# LogicsOnly_Main.net
KiCad netlist of a schematic drawn in Altium Designer
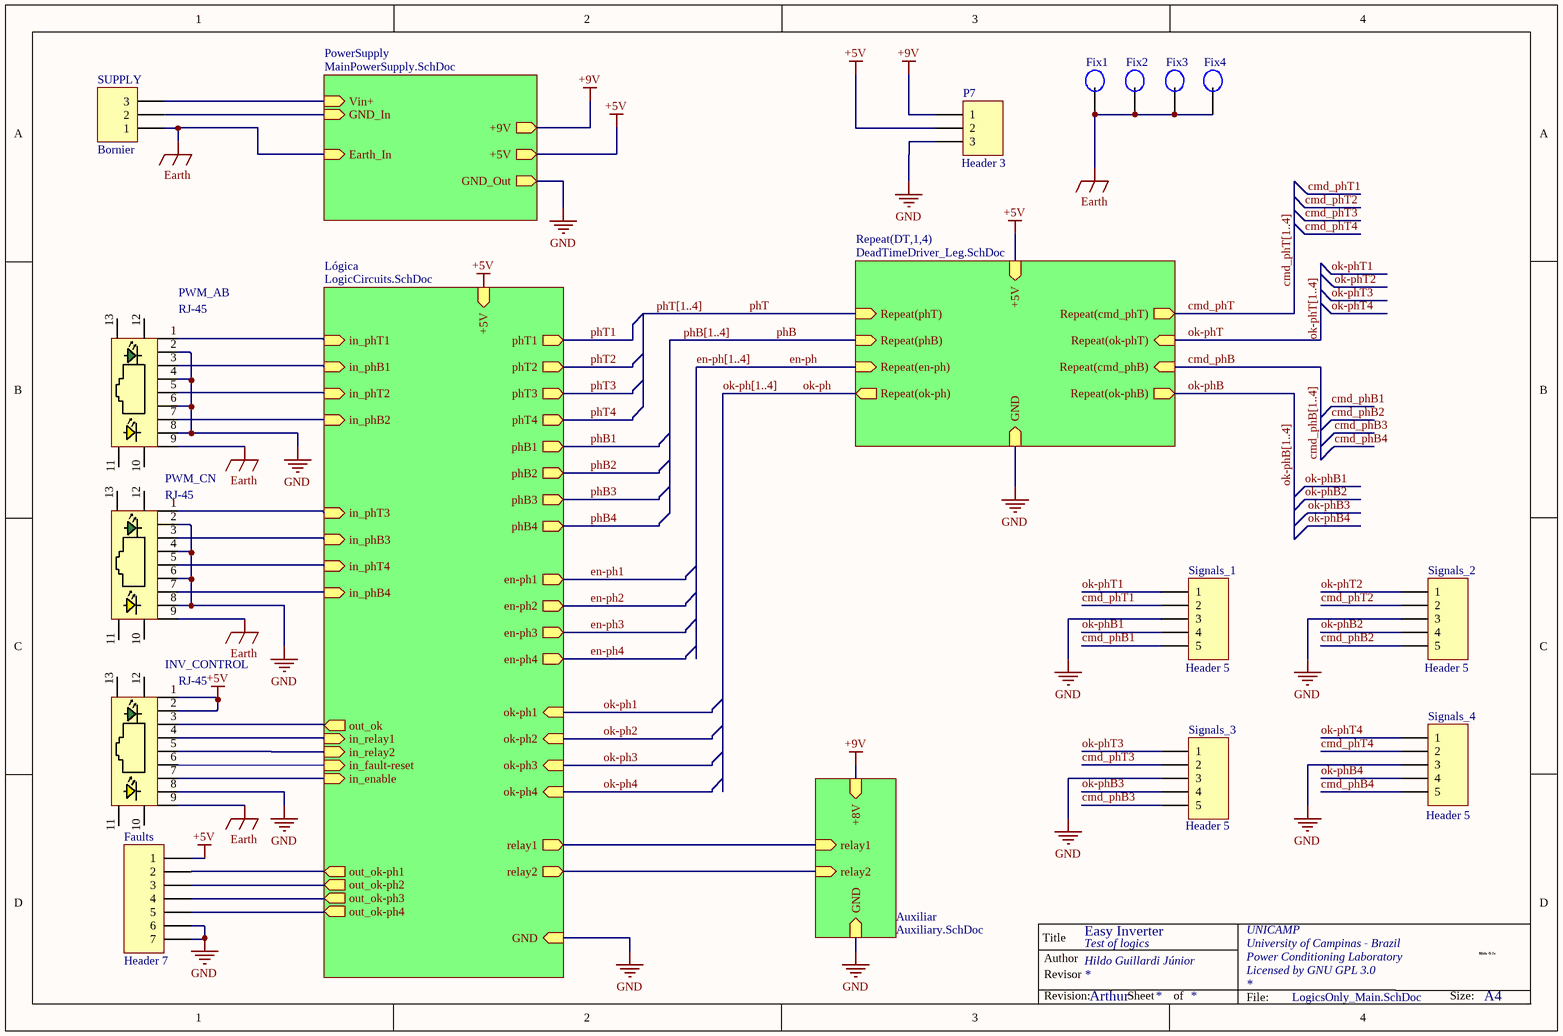
[diagram p0: LogicsOnly_Main.SchDoc]

(export (version "E")
  (design (tool "Eeschema 10.0.6"))
  (components
    (comp (ref "Faults")
      (value "Header 7")
      (description "Header, 7-Pin")
      (libsource (lib "Miscellaneous Connectors") (part "Header 7"))
    )
    (comp (ref "Fix1") (value "~") (footprint "Pino") (libsource (lib "Sch_LCEE") (part "Pino")))
    (comp (ref "Fix2") (value "~") (footprint "Pino") (libsource (lib "Sch_LCEE") (part "Pino")))
    (comp (ref "Fix3") (value "~") (footprint "Pino") (libsource (lib "Sch_LCEE") (part "Pino")))
    (comp (ref "Fix4") (value "~") (footprint "Pino") (libsource (lib "Sch_LCEE") (part "Pino")))
    (comp (ref "INV_CONTROL") (value "RJ-45") (footprint "RJ-45") (libsource (lib "Sch_LCEE") (part "RJ-45")))
    (comp (ref "P7")
      (value "Header 3")
      (footprint "HDR1X3")
      (description "Header, 3-Pin")
      (libsource (lib "") (part "Header 3_1"))
    )
    (comp (ref "PWM_AB") (value "RJ-45") (footprint "RJ-45") (libsource (lib "Sch_LCEE") (part "RJ-45")))
    (comp (ref "PWM_CN") (value "RJ-45") (footprint "RJ-45") (libsource (lib "Sch_LCEE") (part "RJ-45")))
    (comp (ref "Signals_1")
      (value "Header 5")
      (footprint "HDR1X5")
      (description "Header, 5-Pin")
      (libsource (lib "Miscellaneous Connectors") (part "Header 5"))
    )
    (comp (ref "Signals_2")
      (value "Header 5")
      (footprint "HDR1X5")
      (description "Header, 5-Pin")
      (libsource (lib "Miscellaneous Connectors") (part "Header 5"))
    )
    (comp (ref "Signals_3")
      (value "Header 5")
      (footprint "HDR1X5")
      (description "Header, 5-Pin")
      (libsource (lib "Miscellaneous Connectors") (part "Header 5"))
    )
    (comp (ref "Signals_4")
      (value "Header 5")
      (footprint "HDR1X5")
      (description "Header, 5-Pin")
      (libsource (lib "Miscellaneous Connectors") (part "Header 5"))
    )
    (comp (ref "SUPPLY")
      (value "Bornier")
      (footprint "3 Pin  Borner")
      (description "Header, 3-Pin")
      (libsource (lib "AQAC") (part "Header 3"))
    )
  )
  (nets
    (net (code "1") (name "+5V") (class "Default")
      (node (ref "Faults") (pin "1") (pinfunction "1_1") (pintype "passive"))
      (node (ref "INV_CONTROL") (pin "1") (pinfunction "1_1") (pintype "passive"))
      (node (ref "INV_CONTROL") (pin "2") (pinfunction "2_2") (pintype "passive"))
      (node (ref "P7") (pin "2") (pinfunction "2_2") (pintype "passive"))
    )
    (net (code "2") (name "+9V") (class "Default")
      (node (ref "P7") (pin "1") (pinfunction "1_1") (pintype "passive"))
    )
    (net (code "3") (name "/GND_In") (class "Default")
      (node (ref "SUPPLY") (pin "2") (pinfunction "2_2") (pintype "passive"))
    )
    (net (code "4") (name "/Vin+") (class "Default")
      (node (ref "SUPPLY") (pin "3") (pinfunction "3_3") (pintype "passive"))
    )
    (net (code "6") (name "/cmd_phB1") (class "Default")
      (node (ref "Signals_1") (pin "5") (pinfunction "5_5") (pintype "passive"))
    )
    (net (code "7") (name "/cmd_phB2") (class "Default")
      (node (ref "Signals_2") (pin "5") (pinfunction "5_5") (pintype "passive"))
    )
    (net (code "8") (name "/cmd_phB3") (class "Default")
      (node (ref "Signals_3") (pin "5") (pinfunction "5_5") (pintype "passive"))
    )
    (net (code "9") (name "/cmd_phB4") (class "Default")
      (node (ref "Signals_4") (pin "5") (pinfunction "5_5") (pintype "passive"))
    )
    (net (code "12") (name "/cmd_phT1") (class "Default")
      (node (ref "Signals_1") (pin "2") (pinfunction "2_2") (pintype "passive"))
    )
    (net (code "13") (name "/cmd_phT2") (class "Default")
      (node (ref "Signals_2") (pin "2") (pinfunction "2_2") (pintype "passive"))
    )
    (net (code "14") (name "/cmd_phT3") (class "Default")
      (node (ref "Signals_3") (pin "2") (pinfunction "2_2") (pintype "passive"))
    )
    (net (code "15") (name "/cmd_phT4") (class "Default")
      (node (ref "Signals_4") (pin "2") (pinfunction "2_2") (pintype "passive"))
    )
    (net (code "23") (name "/in_enable") (class "Default")
      (node (ref "INV_CONTROL") (pin "7") (pinfunction "7_7") (pintype "passive"))
    )
    (net (code "24") (name "/in_fault-reset") (class "Default")
      (node (ref "INV_CONTROL") (pin "6") (pinfunction "6_6") (pintype "passive"))
    )
    (net (code "25") (name "/in_phB1") (class "Default")
      (node (ref "PWM_AB") (pin "3") (pinfunction "3_3") (pintype "passive"))
    )
    (net (code "26") (name "/in_phB2") (class "Default")
      (node (ref "PWM_AB") (pin "7") (pinfunction "7_7") (pintype "passive"))
    )
    (net (code "27") (name "/in_phB3") (class "Default")
      (node (ref "PWM_CN") (pin "3") (pinfunction "3_3") (pintype "passive"))
    )
    (net (code "28") (name "/in_phB4") (class "Default")
      (node (ref "PWM_CN") (pin "7") (pinfunction "7_7") (pintype "passive"))
    )
    (net (code "29") (name "/in_phT1") (class "Default")
      (node (ref "PWM_AB") (pin "1") (pinfunction "1_1") (pintype "passive"))
    )
    (net (code "30") (name "/in_phT2") (class "Default")
      (node (ref "PWM_AB") (pin "5") (pinfunction "5_5") (pintype "passive"))
    )
    (net (code "31") (name "/in_phT3") (class "Default")
      (node (ref "PWM_CN") (pin "1") (pinfunction "1_1") (pintype "passive"))
    )
    (net (code "32") (name "/in_phT4") (class "Default")
      (node (ref "PWM_CN") (pin "5") (pinfunction "5_5") (pintype "passive"))
    )
    (net (code "33") (name "/in_relay1") (class "Default")
      (node (ref "INV_CONTROL") (pin "4") (pinfunction "4_4") (pintype "passive"))
    )
    (net (code "34") (name "/in_relay2") (class "Default")
      (node (ref "INV_CONTROL") (pin "5") (pinfunction "5_5") (pintype "passive"))
    )
    (net (code "41") (name "/ok-phB1") (class "Default")
      (node (ref "Signals_1") (pin "4") (pinfunction "4_4") (pintype "passive"))
    )
    (net (code "42") (name "/ok-phB2") (class "Default")
      (node (ref "Signals_2") (pin "4") (pinfunction "4_4") (pintype "passive"))
    )
    (net (code "43") (name "/ok-phB3") (class "Default")
      (node (ref "Signals_3") (pin "4") (pinfunction "4_4") (pintype "passive"))
    )
    (net (code "44") (name "/ok-phB4") (class "Default")
      (node (ref "Signals_4") (pin "4") (pinfunction "4_4") (pintype "passive"))
    )
    (net (code "47") (name "/ok-phT1") (class "Default")
      (node (ref "Signals_1") (pin "1") (pinfunction "1_1") (pintype "passive"))
    )
    (net (code "48") (name "/ok-phT2") (class "Default")
      (node (ref "Signals_2") (pin "1") (pinfunction "1_1") (pintype "passive"))
    )
    (net (code "49") (name "/ok-phT3") (class "Default")
      (node (ref "Signals_3") (pin "1") (pinfunction "1_1") (pintype "passive"))
    )
    (net (code "50") (name "/ok-phT4") (class "Default")
      (node (ref "Signals_4") (pin "1") (pinfunction "1_1") (pintype "passive"))
    )
    (net (code "53") (name "/out_ok") (class "Default")
      (node (ref "INV_CONTROL") (pin "3") (pinfunction "3_3") (pintype "passive"))
    )
    (net (code "54") (name "/out_ok-ph1") (class "Default")
      (node (ref "Faults") (pin "2") (pinfunction "2_2") (pintype "passive"))
    )
    (net (code "55") (name "/out_ok-ph2") (class "Default")
      (node (ref "Faults") (pin "3") (pinfunction "3_3") (pintype "passive"))
    )
    (net (code "56") (name "/out_ok-ph3") (class "Default")
      (node (ref "Faults") (pin "4") (pinfunction "4_4") (pintype "passive"))
    )
    (net (code "57") (name "/out_ok-ph4") (class "Default")
      (node (ref "Faults") (pin "5") (pinfunction "5_5") (pintype "passive"))
    )
    (net (code "72") (name "Earth") (class "Default")
      (node (ref "Fix1") (pin "0") (pinfunction "0_0") (pintype "passive"))
      (node (ref "Fix2") (pin "0") (pinfunction "0_0") (pintype "passive"))
      (node (ref "Fix3") (pin "0") (pinfunction "0_0") (pintype "passive"))
      (node (ref "Fix4") (pin "0") (pinfunction "0_0") (pintype "passive"))
      (node (ref "INV_CONTROL") (pin "9") (pinfunction "9_9") (pintype "passive"))
      (node (ref "PWM_AB") (pin "9") (pinfunction "9_9") (pintype "passive"))
      (node (ref "PWM_CN") (pin "9") (pinfunction "9_9") (pintype "passive"))
      (node (ref "SUPPLY") (pin "1") (pinfunction "1_1") (pintype "passive"))
    )
    (net (code "73") (name "GND") (class "Default")
      (node (ref "Faults") (pin "6") (pinfunction "6_6") (pintype "passive"))
      (node (ref "Faults") (pin "7") (pinfunction "7_7") (pintype "passive"))
      (node (ref "INV_CONTROL") (pin "8") (pinfunction "8_8") (pintype "passive"))
      (node (ref "P7") (pin "3") (pinfunction "3_3") (pintype "passive"))
      (node (ref "PWM_AB") (pin "2") (pinfunction "2_2") (pintype "passive"))
      (node (ref "PWM_AB") (pin "4") (pinfunction "4_4") (pintype "passive"))
      (node (ref "PWM_AB") (pin "6") (pinfunction "6_6") (pintype "passive"))
      (node (ref "PWM_AB") (pin "8") (pinfunction "8_8") (pintype "passive"))
      (node (ref "PWM_CN") (pin "2") (pinfunction "2_2") (pintype "passive"))
      (node (ref "PWM_CN") (pin "4") (pinfunction "4_4") (pintype "passive"))
      (node (ref "PWM_CN") (pin "6") (pinfunction "6_6") (pintype "passive"))
      (node (ref "PWM_CN") (pin "8") (pinfunction "8_8") (pintype "passive"))
      (node (ref "Signals_1") (pin "3") (pinfunction "3_3") (pintype "passive"))
      (node (ref "Signals_2") (pin "3") (pinfunction "3_3") (pintype "passive"))
      (node (ref "Signals_3") (pin "3") (pinfunction "3_3") (pintype "passive"))
      (node (ref "Signals_4") (pin "3") (pinfunction "3_3") (pintype "passive"))
    )
    (net (code "74") (name "unconnected-(INV_CONTROL-Pad10)") (class "Default")
      (node (ref "INV_CONTROL") (pin "10") (pinfunction "10_10") (pintype "passive"))
    )
    (net (code "75") (name "unconnected-(INV_CONTROL-Pad11)") (class "Default")
      (node (ref "INV_CONTROL") (pin "11") (pinfunction "11_11") (pintype "passive"))
    )
    (net (code "76") (name "unconnected-(INV_CONTROL-Pad12)") (class "Default")
      (node (ref "INV_CONTROL") (pin "12") (pinfunction "12_12") (pintype "passive"))
    )
    (net (code "77") (name "unconnected-(INV_CONTROL-Pad13)") (class "Default")
      (node (ref "INV_CONTROL") (pin "13") (pinfunction "13_13") (pintype "passive"))
    )
    (net (code "78") (name "unconnected-(PWM_AB-Pad10)") (class "Default")
      (node (ref "PWM_AB") (pin "10") (pinfunction "10_10") (pintype "passive"))
    )
    (net (code "79") (name "unconnected-(PWM_AB-Pad11)") (class "Default")
      (node (ref "PWM_AB") (pin "11") (pinfunction "11_11") (pintype "passive"))
    )
    (net (code "80") (name "unconnected-(PWM_AB-Pad12)") (class "Default")
      (node (ref "PWM_AB") (pin "12") (pinfunction "12_12") (pintype "passive"))
    )
    (net (code "81") (name "unconnected-(PWM_AB-Pad13)") (class "Default")
      (node (ref "PWM_AB") (pin "13") (pinfunction "13_13") (pintype "passive"))
    )
    (net (code "82") (name "unconnected-(PWM_CN-Pad10)") (class "Default")
      (node (ref "PWM_CN") (pin "10") (pinfunction "10_10") (pintype "passive"))
    )
    (net (code "83") (name "unconnected-(PWM_CN-Pad11)") (class "Default")
      (node (ref "PWM_CN") (pin "11") (pinfunction "11_11") (pintype "passive"))
    )
    (net (code "84") (name "unconnected-(PWM_CN-Pad12)") (class "Default")
      (node (ref "PWM_CN") (pin "12") (pinfunction "12_12") (pintype "passive"))
    )
    (net (code "85") (name "unconnected-(PWM_CN-Pad13)") (class "Default")
      (node (ref "PWM_CN") (pin "13") (pinfunction "13_13") (pintype "passive"))
    )
  )
)
